# mcu.net
KiCad netlist of a schematic drawn in Altium Designer
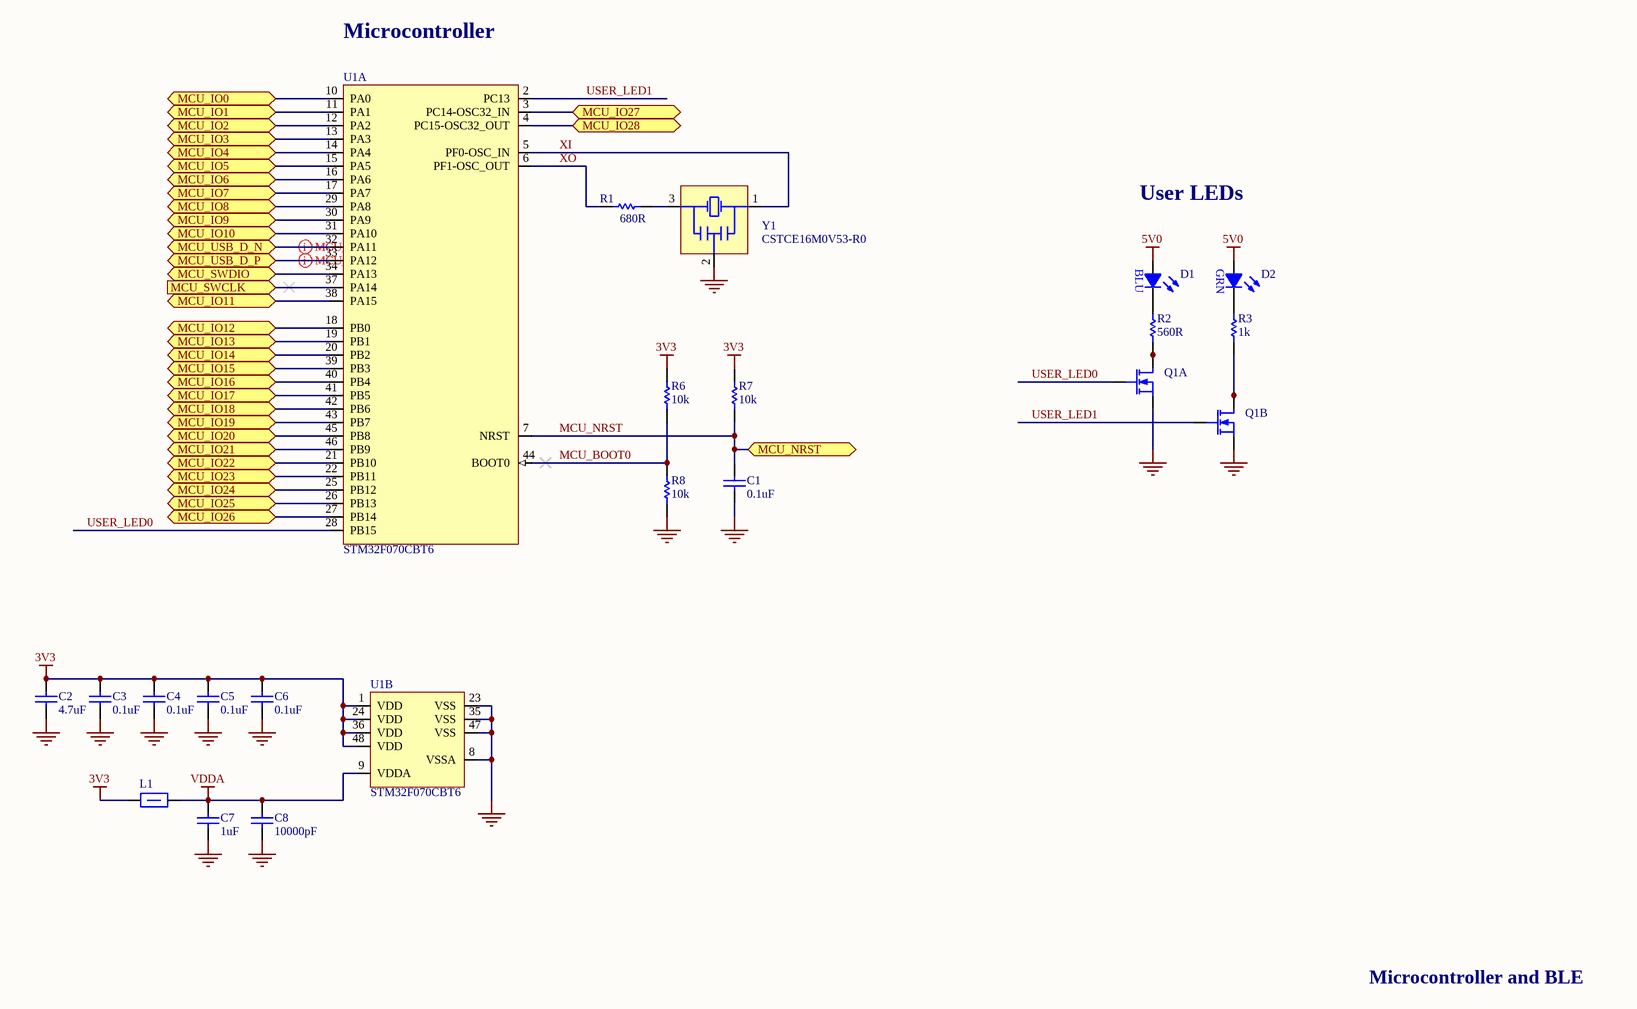
[diagram p0: mcu.SchDoc]

(export (version "E")
  (design (tool "Eeschema 10.0.6"))
  (components
    (comp (ref "C1")
      (value "0.1uF")
      (footprint "C0201")
      (description "CAP CER 0.1UF 16V X5R 0201")
      (fields
        (field (name "MANUFACTURER") "Murata")
        (field (name "MANUFACTURER PART NUMBER") "GRM033R61C104ME84D")
      )
      (libsource (lib "Capacitors") (part "0.1uF 16V 0201"))
    )
    (comp (ref "C2")
      (value "4.7uF")
      (footprint "C0402")
      (description "CAP CER 4.7UF 16V X5R 0402")
      (fields
        (field (name "MANUFACTURER") "Samsung")
        (field (name "MANUFACTURER PART NUMBER") "CL05A475MO5NUNC")
      )
      (libsource (lib "Capacitors") (part "4.7uF 16V 0402"))
    )
    (comp (ref "C3")
      (value "0.1uF")
      (footprint "C0201")
      (description "CAP CER 0.1UF 16V X5R 0201")
      (fields
        (field (name "MANUFACTURER") "Murata")
        (field (name "MANUFACTURER PART NUMBER") "GRM033R61C104ME84D")
      )
      (libsource (lib "Capacitors") (part "0.1uF 16V 0201"))
    )
    (comp (ref "C4")
      (value "0.1uF")
      (footprint "C0201")
      (description "CAP CER 0.1UF 16V X5R 0201")
      (fields
        (field (name "MANUFACTURER") "Murata")
        (field (name "MANUFACTURER PART NUMBER") "GRM033R61C104ME84D")
      )
      (libsource (lib "Capacitors") (part "0.1uF 16V 0201"))
    )
    (comp (ref "C5")
      (value "0.1uF")
      (footprint "C0201")
      (description "CAP CER 0.1UF 16V X5R 0201")
      (fields
        (field (name "MANUFACTURER") "Murata")
        (field (name "MANUFACTURER PART NUMBER") "GRM033R61C104ME84D")
      )
      (libsource (lib "Capacitors") (part "0.1uF 16V 0201"))
    )
    (comp (ref "C6")
      (value "0.1uF")
      (footprint "C0201")
      (description "CAP CER 0.1UF 16V X5R 0201")
      (fields
        (field (name "MANUFACTURER") "Murata")
        (field (name "MANUFACTURER PART NUMBER") "GRM033R61C104ME84D")
      )
      (libsource (lib "Capacitors") (part "0.1uF 16V 0201"))
    )
    (comp (ref "C7")
      (value "1uF")
      (footprint "C0402")
      (description "CAP CER 1UF 25V X5R 0402")
      (fields
        (field (name "MANUFACTURER") "Taiyo Yuden")
        (field (name "MANUFACTURER PART NUMBER") "TMK105BJ105MV-F")
      )
      (libsource (lib "Capacitors") (part "1uF 25V 0402"))
    )
    (comp (ref "C8")
      (value "10000pF")
      (footprint "C0201")
      (description "CAP CER 10000PF 25V X5R 0201")
      (fields
        (field (name "MANUFACTURER") "Murata")
        (field (name "MANUFACTURER PART NUMBER") "GRM033R61E103MA12D")
      )
      (libsource (lib "Capacitors") (part "10000pF 25V 0201"))
    )
    (comp (ref "D1")
      (value "5988091107F")
      (footprint "LED0603")
      (description "LED BLUE CLEAR 0603 SMD")
      (fields
        (field (name "MANUFACTURER") "Dialight")
        (field (name "MANUFACTURER PART NUMBER") "598-8091-107F")
      )
      (libsource (lib "Diodes") (part "Blue 0603 LED"))
    )
    (comp (ref "D2")
      (value "5988070107F")
      (footprint "LED0603")
      (description "LED GREEN CLEAR 0603 SMD")
      (fields
        (field (name "MANUFACTURER") "Dialight")
        (field (name "MANUFACTURER PART NUMBER") "598-8070-107F")
      )
      (libsource (lib "Diodes") (part "Green 0603 LED"))
    )
    (comp (ref "L1")
      (value "BLM15AG601SN1D")
      (footprint "L0402")
      (description "FERRITE BEAD 600 OHM 0402 1LN")
      (fields (field (name "MANUFACTURER") "Murata") (field (name "TOLERANCE") "25%"))
      (libsource (lib "Inductors") (part "BLM15AG601SN1D"))
    )
    (comp (ref "Q1")
      (value "PMDXB600UNE")
      (footprint "NXP_DFN1010B-6")
      (description "MOSFET 2N-CH 20V 0.6A 6DFN")
      (fields (field (name "MANUFACTURER") "NXP Semiconductors"))
      (libsource (lib "ICs") (part "PMDXB600UNE"))
    )
    (comp (ref "R1")
      (value "680R")
      (footprint "R0201")
      (description "RES SMD 680 OHM 1% 1/20W 0201")
      (fields
        (field (name "MANUFACTURER") "Yageo")
        (field (name "MANUFACTURER PART NUMBER") "RC0201FR-07680RL")
      )
      (libsource (lib "Resistors") (part "680R 0201"))
    )
    (comp (ref "R2")
      (value "560R")
      (footprint "R0201")
      (description "RES SMD 560 OHM 1% 1/20W 0201")
      (fields
        (field (name "MANUFACTURER") "Panasonic ECG")
        (field (name "MANUFACTURER PART NUMBER") "ERJ-1GEF5600C")
      )
      (libsource (lib "Resistors") (part "560R 0201"))
    )
    (comp (ref "R3")
      (value "1k")
      (footprint "R0201")
      (description "RES SMD 1K OHM 1% 1/20W 0201")
      (fields
        (field (name "MANUFACTURER") "Panasonic ECG")
        (field (name "MANUFACTURER PART NUMBER") "ERJ-1GEF1001C")
      )
      (libsource (lib "Resistors") (part "1k 0201"))
    )
    (comp (ref "R6")
      (value "10k")
      (footprint "R0201")
      (description "RES SMD 10K OHM 1% 1/20W 0201")
      (fields
        (field (name "MANUFACTURER") "Panasonic ECG")
        (field (name "MANUFACTURER PART NUMBER") "ERJ-1GEF1002C")
      )
      (libsource (lib "Resistors") (part "10k 0201"))
    )
    (comp (ref "R7")
      (value "10k")
      (footprint "R0201")
      (description "RES SMD 10K OHM 1% 1/20W 0201")
      (fields
        (field (name "MANUFACTURER") "Panasonic ECG")
        (field (name "MANUFACTURER PART NUMBER") "ERJ-1GEF1002C")
      )
      (libsource (lib "Resistors") (part "10k 0201"))
    )
    (comp (ref "R8")
      (value "10k")
      (footprint "R0201")
      (description "RES SMD 10K OHM 1% 1/20W 0201")
      (fields
        (field (name "MANUFACTURER") "Panasonic ECG")
        (field (name "MANUFACTURER PART NUMBER") "ERJ-1GEF1002C")
      )
      (libsource (lib "Resistors") (part "10k 0201"))
    )
    (comp (ref "U1")
      (value "STM32F070CBT6")
      (footprint "STM_LQFP48")
      (description "IC MCU 32BIT 128KB FLASH 48LQFP")
      (fields (field (name "MANUFACTURER") "STMicroelectronics"))
      (libsource (lib "") (part "STM32F070CBT6_1"))
    )
    (comp (ref "Y1")
      (value "CSTCE16M0V53-R0")
      (footprint "MUR_CSTCE_V")
      (description "CER RES 16.0000MHZ 15PF SMD")
      (fields (field (name "MANUFACTURER") "Murata") (field (name "TOLERANCE") "0.5%"))
      (libsource (lib "Oscillators") (part "16MHz Resonator"))
    )
  )
  (nets
    (net (code "1") (name "/MCU_BOOT0") (class "Default")
      (node (ref "R6") (pin "1") (pinfunction "1_1") (pintype "passive"))
      (node (ref "R8") (pin "2") (pinfunction "2_2") (pintype "passive"))
      (node (ref "U1") (pin "44") (pinfunction "BOOT0_44") (pintype "input"))
    )
    (net (code "2") (name "/MCU_IO0") (class "Default")
      (node (ref "U1") (pin "10") (pinfunction "PA0_10") (pintype "bidirectional"))
    )
    (net (code "3") (name "/MCU_IO1") (class "Default")
      (node (ref "U1") (pin "11") (pinfunction "PA1_11") (pintype "bidirectional"))
    )
    (net (code "4") (name "/MCU_IO2") (class "Default")
      (node (ref "U1") (pin "12") (pinfunction "PA2_12") (pintype "bidirectional"))
    )
    (net (code "5") (name "/MCU_IO3") (class "Default")
      (node (ref "U1") (pin "13") (pinfunction "PA3_13") (pintype "bidirectional"))
    )
    (net (code "6") (name "/MCU_IO4") (class "Default")
      (node (ref "U1") (pin "14") (pinfunction "PA4_14") (pintype "bidirectional"))
    )
    (net (code "7") (name "/MCU_IO5") (class "Default")
      (node (ref "U1") (pin "15") (pinfunction "PA5_15") (pintype "bidirectional"))
    )
    (net (code "8") (name "/MCU_IO6") (class "Default")
      (node (ref "U1") (pin "16") (pinfunction "PA6_16") (pintype "bidirectional"))
    )
    (net (code "9") (name "/MCU_IO7") (class "Default")
      (node (ref "U1") (pin "17") (pinfunction "PA7_17") (pintype "bidirectional"))
    )
    (net (code "10") (name "/MCU_IO8") (class "Default")
      (node (ref "U1") (pin "29") (pinfunction "PA8_29") (pintype "bidirectional"))
    )
    (net (code "11") (name "/MCU_IO9") (class "Default")
      (node (ref "U1") (pin "30") (pinfunction "PA9_30") (pintype "bidirectional"))
    )
    (net (code "12") (name "/MCU_IO10") (class "Default")
      (node (ref "U1") (pin "31") (pinfunction "PA10_31") (pintype "bidirectional"))
    )
    (net (code "13") (name "/MCU_IO11") (class "Default")
      (node (ref "U1") (pin "38") (pinfunction "PA15_38") (pintype "bidirectional"))
    )
    (net (code "14") (name "/MCU_IO12") (class "Default")
      (node (ref "U1") (pin "18") (pinfunction "PB0_18") (pintype "bidirectional"))
    )
    (net (code "15") (name "/MCU_IO13") (class "Default")
      (node (ref "U1") (pin "19") (pinfunction "PB1_19") (pintype "bidirectional"))
    )
    (net (code "16") (name "/MCU_IO14") (class "Default")
      (node (ref "U1") (pin "20") (pinfunction "PB2_20") (pintype "bidirectional"))
    )
    (net (code "17") (name "/MCU_IO15") (class "Default")
      (node (ref "U1") (pin "39") (pinfunction "PB3_39") (pintype "bidirectional"))
    )
    (net (code "18") (name "/MCU_IO16") (class "Default")
      (node (ref "U1") (pin "40") (pinfunction "PB4_40") (pintype "bidirectional"))
    )
    (net (code "19") (name "/MCU_IO17") (class "Default")
      (node (ref "U1") (pin "41") (pinfunction "PB5_41") (pintype "bidirectional"))
    )
    (net (code "20") (name "/MCU_IO18") (class "Default")
      (node (ref "U1") (pin "42") (pinfunction "PB6_42") (pintype "bidirectional"))
    )
    (net (code "21") (name "/MCU_IO19") (class "Default")
      (node (ref "U1") (pin "43") (pinfunction "PB7_43") (pintype "bidirectional"))
    )
    (net (code "22") (name "/MCU_IO20") (class "Default")
      (node (ref "U1") (pin "45") (pinfunction "PB8_45") (pintype "bidirectional"))
    )
    (net (code "23") (name "/MCU_IO21") (class "Default")
      (node (ref "U1") (pin "46") (pinfunction "PB9_46") (pintype "bidirectional"))
    )
    (net (code "24") (name "/MCU_IO22") (class "Default")
      (node (ref "U1") (pin "21") (pinfunction "PB10_21") (pintype "bidirectional"))
    )
    (net (code "25") (name "/MCU_IO23") (class "Default")
      (node (ref "U1") (pin "22") (pinfunction "PB11_22") (pintype "bidirectional"))
    )
    (net (code "26") (name "/MCU_IO24") (class "Default")
      (node (ref "U1") (pin "25") (pinfunction "PB12_25") (pintype "bidirectional"))
    )
    (net (code "27") (name "/MCU_IO25") (class "Default")
      (node (ref "U1") (pin "26") (pinfunction "PB13_26") (pintype "bidirectional"))
    )
    (net (code "28") (name "/MCU_IO26") (class "Default")
      (node (ref "U1") (pin "27") (pinfunction "PB14_27") (pintype "bidirectional"))
    )
    (net (code "29") (name "/MCU_IO27") (class "Default")
      (node (ref "U1") (pin "3") (pinfunction "PC14-OSC32_IN_3") (pintype "bidirectional"))
    )
    (net (code "30") (name "/MCU_IO28") (class "Default")
      (node (ref "U1") (pin "4") (pinfunction "PC15-OSC32_OUT_4") (pintype "bidirectional"))
    )
    (net (code "31") (name "/MCU_NRST") (class "Default")
      (node (ref "C1") (pin "2") (pinfunction "2_2") (pintype "passive"))
      (node (ref "R7") (pin "1") (pinfunction "1_1") (pintype "passive"))
      (node (ref "U1") (pin "7") (pinfunction "NRST_7") (pintype "bidirectional"))
    )
    (net (code "32") (name "/MCU_SWCLK") (class "Default")
      (node (ref "U1") (pin "37") (pinfunction "PA14_37") (pintype "bidirectional"))
    )
    (net (code "33") (name "/MCU_SWDIO") (class "Default")
      (node (ref "U1") (pin "34") (pinfunction "PA13_34") (pintype "bidirectional"))
    )
    (net (code "34") (name "/MCU_USB_D_N") (class "Default")
      (node (ref "U1") (pin "32") (pinfunction "PA11_32") (pintype "bidirectional"))
    )
    (net (code "35") (name "/MCU_USB_D_P") (class "Default")
      (node (ref "U1") (pin "33") (pinfunction "PA12_33") (pintype "bidirectional"))
    )
    (net (code "36") (name "/USER_LED0") (class "Default")
      (node (ref "Q1") (pin "2") (pinfunction "G1_2") (pintype "passive"))
      (node (ref "U1") (pin "28") (pinfunction "PB15_28") (pintype "bidirectional"))
    )
    (net (code "37") (name "/USER_LED1") (class "Default")
      (node (ref "Q1") (pin "5") (pinfunction "G2_5") (pintype "passive"))
      (node (ref "U1") (pin "2") (pinfunction "PC13_2") (pintype "bidirectional"))
    )
    (net (code "38") (name "/XI") (class "Default")
      (node (ref "U1") (pin "5") (pinfunction "PF0-OSC_IN_5") (pintype "bidirectional"))
      (node (ref "Y1") (pin "1") (pinfunction "1_1") (pintype "passive"))
    )
    (net (code "39") (name "/XO") (class "Default")
      (node (ref "R1") (pin "1") (pinfunction "1_1") (pintype "passive"))
      (node (ref "U1") (pin "6") (pinfunction "PF1-OSC_OUT_6") (pintype "bidirectional"))
    )
    (net (code "40") (name "3V3") (class "Default")
      (node (ref "C2") (pin "2") (pinfunction "2_2") (pintype "passive"))
      (node (ref "C3") (pin "2") (pinfunction "2_2") (pintype "passive"))
      (node (ref "C4") (pin "2") (pinfunction "2_2") (pintype "passive"))
      (node (ref "C5") (pin "2") (pinfunction "2_2") (pintype "passive"))
      (node (ref "C6") (pin "2") (pinfunction "2_2") (pintype "passive"))
      (node (ref "L1") (pin "1") (pinfunction "1_1") (pintype "passive"))
      (node (ref "R6") (pin "2") (pinfunction "2_2") (pintype "passive"))
      (node (ref "R7") (pin "2") (pinfunction "2_2") (pintype "passive"))
      (node (ref "U1") (pin "1") (pinfunction "VDD_1") (pintype "power_in"))
      (node (ref "U1") (pin "24") (pinfunction "VDD_24") (pintype "power_in"))
      (node (ref "U1") (pin "36") (pinfunction "VDD_36") (pintype "power_in"))
      (node (ref "U1") (pin "48") (pinfunction "VDD_48") (pintype "power_in"))
    )
    (net (code "41") (name "5V0") (class "Default")
      (node (ref "D1") (pin "2") (pinfunction "A_2") (pintype "passive"))
      (node (ref "D2") (pin "2") (pinfunction "A_2") (pintype "passive"))
    )
    (net (code "42") (name "GND") (class "Default")
      (node (ref "C1") (pin "1") (pinfunction "1_1") (pintype "passive"))
      (node (ref "C2") (pin "1") (pinfunction "1_1") (pintype "passive"))
      (node (ref "C3") (pin "1") (pinfunction "1_1") (pintype "passive"))
      (node (ref "C4") (pin "1") (pinfunction "1_1") (pintype "passive"))
      (node (ref "C5") (pin "1") (pinfunction "1_1") (pintype "passive"))
      (node (ref "C6") (pin "1") (pinfunction "1_1") (pintype "passive"))
      (node (ref "C7") (pin "1") (pinfunction "1_1") (pintype "passive"))
      (node (ref "C8") (pin "1") (pinfunction "1_1") (pintype "passive"))
      (node (ref "Q1") (pin "1") (pinfunction "S1_1") (pintype "passive"))
      (node (ref "Q1") (pin "4") (pinfunction "S2_4") (pintype "passive"))
      (node (ref "R8") (pin "1") (pinfunction "1_1") (pintype "passive"))
      (node (ref "U1") (pin "23") (pinfunction "VSS_23") (pintype "power_in"))
      (node (ref "U1") (pin "35") (pinfunction "VSS_35") (pintype "power_in"))
      (node (ref "U1") (pin "47") (pinfunction "VSS_47") (pintype "power_in"))
      (node (ref "U1") (pin "8") (pinfunction "VSSA_8") (pintype "power_in"))
      (node (ref "Y1") (pin "2") (pinfunction "2_2") (pintype "passive"))
    )
    (net (code "43") (name "Net-(D1-K)") (class "Default")
      (node (ref "D1") (pin "1") (pinfunction "K_1") (pintype "passive"))
      (node (ref "R2") (pin "2") (pinfunction "2_2") (pintype "passive"))
    )
    (net (code "44") (name "Net-(D2-K)") (class "Default")
      (node (ref "D2") (pin "1") (pinfunction "K_1") (pintype "passive"))
      (node (ref "R3") (pin "2") (pinfunction "2_2") (pintype "passive"))
    )
    (net (code "45") (name "Net-(Q1A-D1-Pad6)") (class "Default")
      (node (ref "Q1") (pin "6") (pinfunction "D1_6") (pintype "passive"))
      (node (ref "Q1") (pin "7") (pinfunction "D1_7") (pintype "passive"))
      (node (ref "R2") (pin "1") (pinfunction "1_1") (pintype "passive"))
    )
    (net (code "46") (name "Net-(Q1B-D2-Pad3)") (class "Default")
      (node (ref "Q1") (pin "3") (pinfunction "D2_3") (pintype "passive"))
      (node (ref "Q1") (pin "8") (pinfunction "D2_8") (pintype "passive"))
      (node (ref "R3") (pin "1") (pinfunction "1_1") (pintype "passive"))
    )
    (net (code "47") (name "Net-(R1-Pad2)") (class "Default")
      (node (ref "R1") (pin "2") (pinfunction "2_2") (pintype "passive"))
      (node (ref "Y1") (pin "3") (pinfunction "3_3") (pintype "passive"))
    )
    (net (code "48") (name "VDDA") (class "Default")
      (node (ref "C7") (pin "2") (pinfunction "2_2") (pintype "passive"))
      (node (ref "C8") (pin "2") (pinfunction "2_2") (pintype "passive"))
      (node (ref "L1") (pin "2") (pinfunction "2_2") (pintype "passive"))
      (node (ref "U1") (pin "9") (pinfunction "VDDA_9") (pintype "power_in"))
    )
  )
)
